# PWRBankCharger.net
KiCad netlist of a schematic drawn in Altium Designer
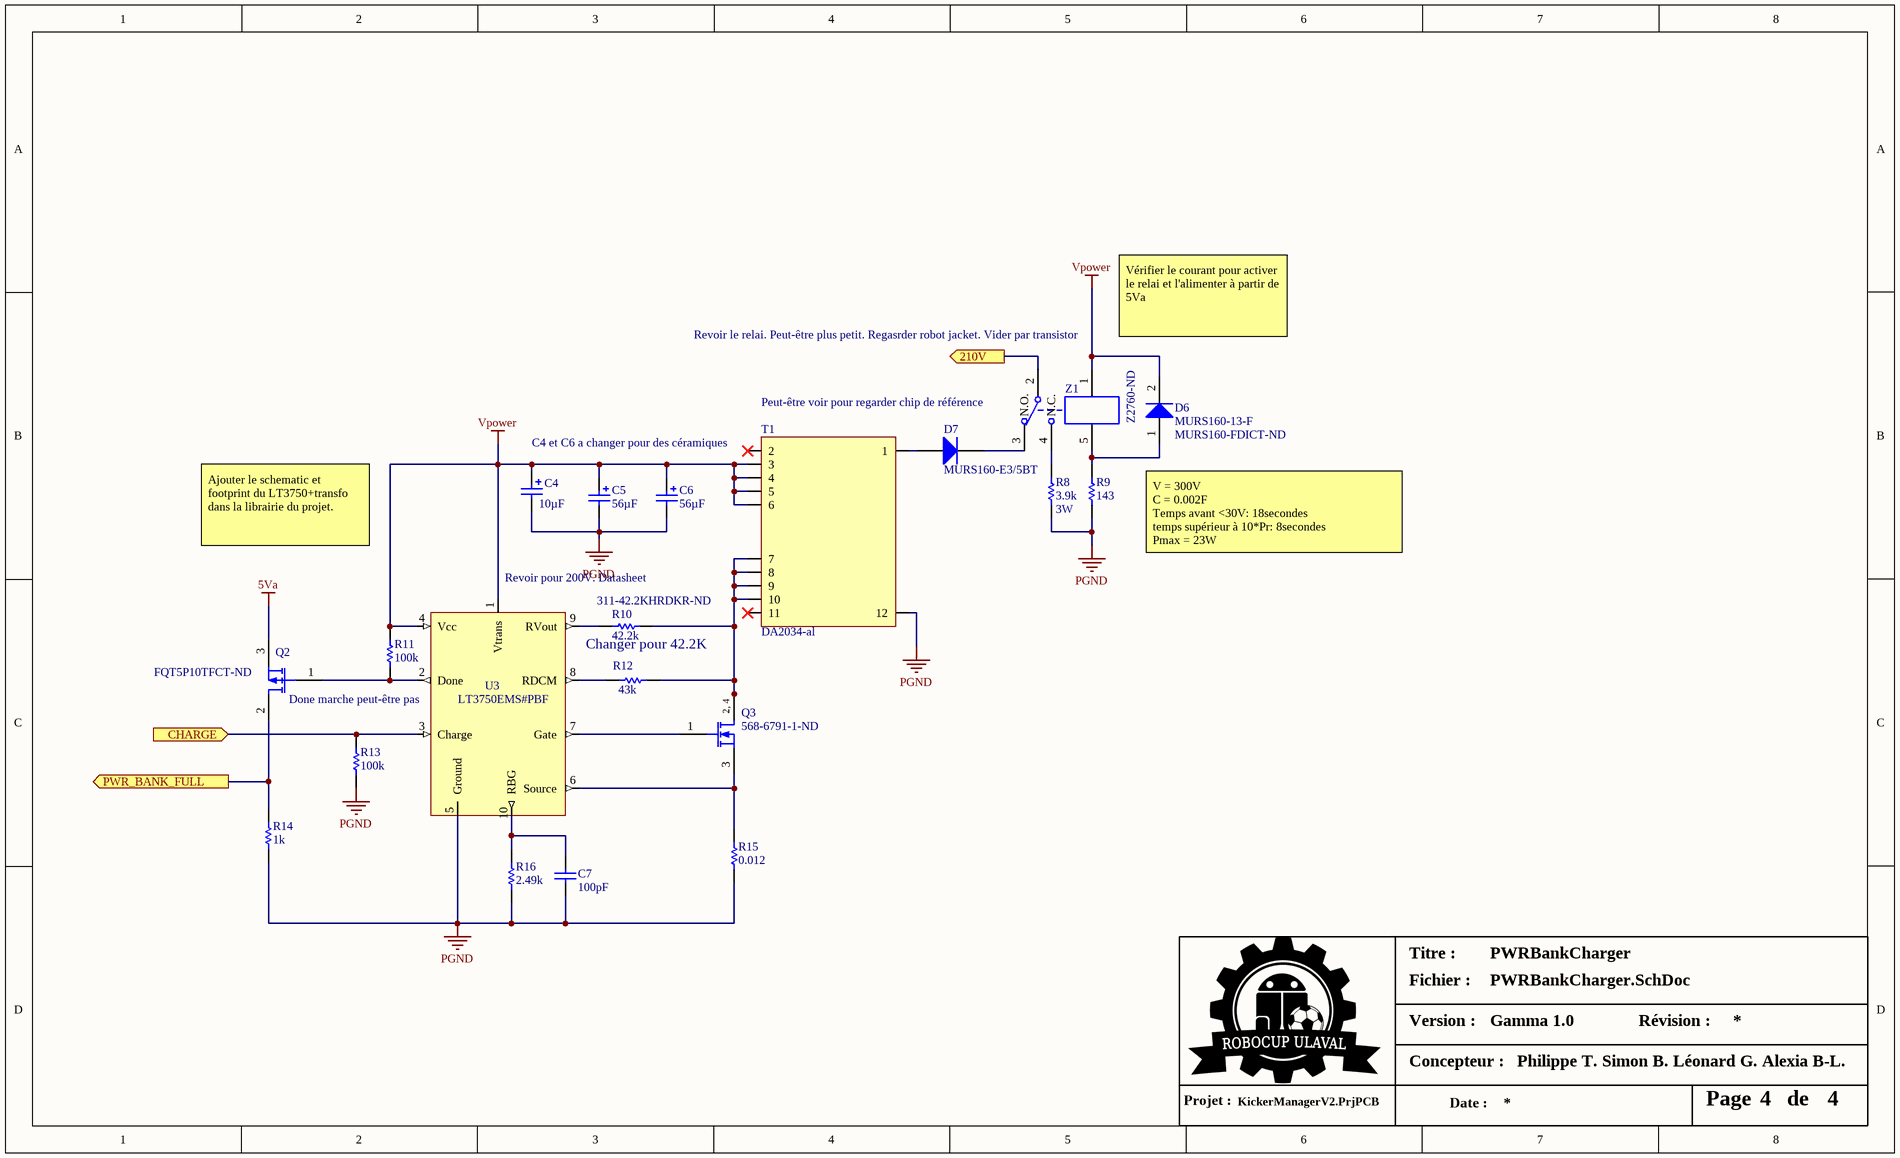
[diagram p0: PWRBankCharger.SchDoc]

(export (version "E")
  (design (tool "Eeschema 10.0.6"))
  (components
    (comp (ref "C4")
      (value "865230340001")
      (footprint "0603")
      (description "CAP 10 UF 20% 16 V")
      (fields
        (field (name "MANUFACTURER") "Wurth Electronics Inc")
        (field (name "CAPACITANCE") "10µF")
        (field (name "TOLERANCE") "±20%")
      )
      (libsource (lib "ResCap") (part "865230340001"))
    )
    (comp (ref "C5")
      (value "865080545010")
      (footprint "CAP 6.6x6.6mm")
      (description "CAP 56 UF 20% 35 V")
      (fields
        (field (name "MANUFACTURER") "Wurth Electronics Inc")
        (field (name "TOLERANCE") "±20%")
        (field (name "CAPACITANCE") "56µF")
      )
      (libsource (lib "ResCap") (part "865080545010"))
    )
    (comp (ref "C6")
      (value "865080545010")
      (footprint "0603")
      (description "CAP 56 UF 20% 35 V")
      (fields
        (field (name "MANUFACTURER") "Wurth Electronics Inc")
        (field (name "TOLERANCE") "±20%")
        (field (name "CAPACITANCE") "56µF")
      )
      (libsource (lib "ResCap") (part "865080545010"))
    )
    (comp (ref "C7")
      (value "CL10B101KB8NNNC")
      (footprint "0603")
      (description "CAP CER 100PF 50V X7R 0603")
      (fields
        (field (name "MANUFACTURER") "Samsung Electro-Mechanics America, Inc.")
        (field (name "TOLERANCE") "±10%")
        (field (name "CAPACITANCE") "100pF")
      )
      (libsource (lib "ResCap") (part "CL10B101KB8NNNC"))
    )
    (comp (ref "D6")
      (value "MURS160-13-F")
      (footprint "SMB")
      (description "DIODE GEN PURP 600V 1A SMB")
      (fields
        (field (name "MANUFACTURER") "Diodes Incorporated")
        (field (name "SUPPLIER PART NUMBER 1") "MURS160-FDICT-ND")
      )
      (libsource (lib "gamma_gestionkicker") (part "MURS160-13-F"))
    )
    (comp (ref "D7")
      (value "MURS160-E3/5BT")
      (footprint "SMB")
      (description "DIODE GEN PURP 600V 2A DO214AA")
      (fields (field (name "MANUFACTURER") "Vishay Semiconductor Diodes Division"))
      (libsource (lib "gamma_gestionkicker") (part "MURS160-E3/5BT"))
    )
    (comp (ref "Q2")
      (value "FQT5P10TF")
      (footprint "SOT-223")
      (description "MOSFET P-CH 100V 1A SOT-223")
      (fields
        (field (name "MANUFACTURER") "Fairchild Semiconductor")
        (field (name "SUPPLIER PART NUMBER 1") "FQT5P10TFCT-ND")
      )
      (libsource (lib "gamma_gestionkicker") (part "FQT5P10TF"))
    )
    (comp (ref "Q3")
      (value "PHT6NQ10T,135")
      (footprint "SOT-223")
      (description "MOSFET N-CH 100V 3A SOT223")
      (fields
        (field (name "MANUFACTURER") "NXP Semiconductors")
        (field (name "SUPPLIER PART NUMBER 1") "568-6791-1-ND")
      )
      (libsource (lib "gamma_gestionkicker") (part "PHT6NQ10T,135"))
    )
    (comp (ref "R8")
      (value "RWM04103901JR15E1")
      (footprint "RWM4x10")
      (description "RES WIREWOUND 3.9K OHM 3W")
      (fields
        (field (name "MANUFACTURER") "Vishay Sfernice")
        (field (name "TOLERANCE") "±5%")
        (field (name "RESISTANCE (OHMS)") "3.9k")
        (field (name "POWER (WATTS)") "3W")
      )
      (libsource (lib "gamma_gestionkicker") (part "RWM04103901JR15E1"))
    )
    (comp (ref "R9")
      (value "CRCW1206143RFKEA")
      (footprint "1206")
      (description "RES SMD 143 OHM 1% 1/4W 1206")
      (fields
        (field (name "MANUFACTURER") "Vishay Dale")
        (field (name "TOLERANCE") "±1%")
        (field (name "RESISTANCE (OHMS)") "143")
      )
      (libsource (lib "ResCap") (part "CRCW1206143RFKEA"))
    )
    (comp (ref "R10")
      (value "RC0603FR-0760K4L")
      (footprint "0603")
      (description "RES SMD 42.2K OHM 1% 1/10W 0603")
      (fields
        (field (name "MANUFACTURER") "Yageo")
        (field (name "TOLERANCE") "±1%")
        (field (name "RESISTANCE (OHMS)") "42.2k")
        (field (name "SUPPLIER PART NUMBER 1") "311-42.2KHRDKR-ND")
      )
      (libsource (lib "ResCap") (part "RC0603FR-0760K4L"))
    )
    (comp (ref "R11")
      (value "RC0603JR-07100KL")
      (footprint "0603")
      (description "RES SMD 100K OHM 5% 1/10W 0603")
      (fields
        (field (name "MANUFACTURER") "Yageo")
        (field (name "TOLERANCE") "±5%")
        (field (name "RESISTANCE (OHMS)") "100k")
      )
      (libsource (lib "ResCap") (part "RC0603JR-07100KL"))
    )
    (comp (ref "R12")
      (value "RC0603JR-0743KL")
      (footprint "0603")
      (description "RES SMD 43K OHM 5% 1/10W 0603")
      (fields
        (field (name "MANUFACTURER") "Yageo")
        (field (name "TOLERANCE") "±5%")
        (field (name "RESISTANCE (OHMS)") "43k")
      )
      (libsource (lib "ResCap") (part "RC0603JR-0743KL"))
    )
    (comp (ref "R13")
      (value "RC0603JR-07100KL")
      (footprint "0603")
      (description "RES SMD 100K OHM 5% 1/10W 0603")
      (fields
        (field (name "MANUFACTURER") "Yageo")
        (field (name "TOLERANCE") "±5%")
        (field (name "RESISTANCE (OHMS)") "100k")
      )
      (libsource (lib "ResCap") (part "RC0603JR-07100KL"))
    )
    (comp (ref "R14")
      (value "RC0603JR-071KL")
      (footprint "0603")
      (description "RES SMD 1K OHM 5% 1/10W 0603")
      (fields
        (field (name "MANUFACTURER") "Yageo")
        (field (name "TOLERANCE") "±5%")
        (field (name "RESISTANCE (OHMS)") "1k")
      )
      (libsource (lib "ResCap") (part "RC0603JR-071KL"))
    )
    (comp (ref "R15")
      (value "RL1220T-R012-J")
      (footprint "0805")
      (description "RES SMD 0.012 OHM 5% 1/4W 0805")
      (fields
        (field (name "MANUFACTURER") "Susumu")
        (field (name "TOLERANCE") "±5%")
        (field (name "RESISTANCE (OHMS)") "0.012")
      )
      (libsource (lib "ResCap") (part "RL1220T-R012-J"))
    )
    (comp (ref "R16")
      (value "RC0603FR-072K49L")
      (footprint "0603")
      (description "RES SMD 2.49K OHM 1% 1/10W 0603")
      (fields
        (field (name "MANUFACTURER") "Yageo")
        (field (name "TOLERANCE") "±1%")
        (field (name "RESISTANCE (OHMS)") "2.49k")
      )
      (libsource (lib "ResCap") (part "RC0603FR-072K49L"))
    )
    (comp (ref "T1")
      (value "DA2034-al")
      (footprint "da2034")
      (libsource (lib "da2034-al") (part "DA2034-al"))
    )
    (comp (ref "U3")
      (value "LT3750EMS#PBF")
      (footprint "MSOP-10")
      (description "IC CONVERTER 10-MSOP")
      (fields (field (name "MANUFACTURER") "Linear Technology"))
      (libsource (lib "gamma_gestionkicker") (part "LT3750EMS#PBF"))
    )
    (comp (ref "Z1")
      (value "G6RL-1 DC12")
      (footprint "G6RL")
      (description "RELAY GEN PURPOSE SPDT 8A 12V")
      (fields
        (field (name "MANUFACTURER") "Omron Electronics Inc-EMC Div")
        (field (name "SUPPLIER PART NUMBER 1") "Z2760-ND")
      )
      (libsource (lib "gamma_gestionkicker") (part "G6RL-1 DC12"))
    )
  )
  (nets
    (net (code "1") (name "/210V") (class "Default")
      (node (ref "Z1") (pin "2") (pinfunction "Signal_Input_2") (pintype "passive"))
    )
    (net (code "2") (name "/CHARGE") (class "Default")
      (node (ref "R13") (pin "2") (pinfunction "2_2") (pintype "passive"))
      (node (ref "U3") (pin "3") (pinfunction "Charge_3") (pintype "input"))
    )
    (net (code "3") (name "/PWR_BANK_FULL") (class "Default")
      (node (ref "Q2") (pin "2") (pinfunction "D_2") (pintype "passive"))
      (node (ref "R14") (pin "2") (pinfunction "2_2") (pintype "passive"))
    )
    (net (code "4") (name "5Va") (class "Default")
      (node (ref "Q2") (pin "3") (pinfunction "S_3") (pintype "passive"))
    )
    (net (code "5") (name "Net-(D6-A)") (class "Default")
      (node (ref "D6") (pin "1") (pinfunction "A_1") (pintype "passive"))
      (node (ref "R9") (pin "1") (pinfunction "1_1") (pintype "passive"))
      (node (ref "Z1") (pin "5") (pinfunction "Coil_Input_-_5") (pintype "passive"))
    )
    (net (code "6") (name "Net-(D7-A)") (class "Default")
      (node (ref "D7") (pin "1") (pinfunction "A_1") (pintype "passive"))
      (node (ref "T1") (pin "1") (pinfunction "1_1") (pintype "passive"))
    )
    (net (code "7") (name "Net-(D7-K)") (class "Default")
      (node (ref "D7") (pin "2") (pinfunction "K_2") (pintype "passive"))
      (node (ref "Z1") (pin "3") (pinfunction "N.O._3") (pintype "passive"))
    )
    (net (code "8") (name "Net-(Q2-G)") (class "Default")
      (node (ref "Q2") (pin "1") (pinfunction "G_1") (pintype "passive"))
      (node (ref "R11") (pin "1") (pinfunction "1_1") (pintype "passive"))
      (node (ref "U3") (pin "2") (pinfunction "Done_2") (pintype "output"))
    )
    (net (code "9") (name "Net-(Q3-D-Pad2)") (class "Default")
      (node (ref "Q3") (pin "2") (pinfunction "D_2") (pintype "passive"))
      (node (ref "Q3") (pin "4") (pinfunction "D_4") (pintype "passive"))
      (node (ref "R10") (pin "2") (pinfunction "2_2") (pintype "passive"))
      (node (ref "R12") (pin "1") (pinfunction "1_1") (pintype "passive"))
      (node (ref "T1") (pin "10") (pinfunction "10_10") (pintype "passive"))
      (node (ref "T1") (pin "7") (pinfunction "7_7") (pintype "passive"))
      (node (ref "T1") (pin "8") (pinfunction "8_8") (pintype "passive"))
      (node (ref "T1") (pin "9") (pinfunction "9_9") (pintype "passive"))
    )
    (net (code "10") (name "Net-(Q3-G)") (class "Default")
      (node (ref "Q3") (pin "1") (pinfunction "G_1") (pintype "passive"))
      (node (ref "U3") (pin "7") (pinfunction "Gate_7") (pintype "output"))
    )
    (net (code "11") (name "Net-(Q3-S)") (class "Default")
      (node (ref "Q3") (pin "3") (pinfunction "S_3") (pintype "passive"))
      (node (ref "R15") (pin "2") (pinfunction "2_2") (pintype "passive"))
      (node (ref "U3") (pin "6") (pinfunction "Source_6") (pintype "output"))
    )
    (net (code "12") (name "Net-(U3-RBG)") (class "Default")
      (node (ref "C7") (pin "1") (pinfunction "1_1") (pintype "passive"))
      (node (ref "R16") (pin "2") (pinfunction "2_2") (pintype "passive"))
      (node (ref "U3") (pin "10") (pinfunction "RBG_10") (pintype "output"))
    )
    (net (code "13") (name "Net-(U3-RDCM)") (class "Default")
      (node (ref "R12") (pin "2") (pinfunction "2_2") (pintype "passive"))
      (node (ref "U3") (pin "8") (pinfunction "RDCM_8") (pintype "output"))
    )
    (net (code "14") (name "Net-(U3-RVout)") (class "Default")
      (node (ref "R10") (pin "1") (pinfunction "1_1") (pintype "passive"))
      (node (ref "U3") (pin "9") (pinfunction "RVout_9") (pintype "output"))
    )
    (net (code "15") (name "Net-(Z1-N.C.)") (class "Default")
      (node (ref "R8") (pin "2") (pinfunction "2_2") (pintype "passive"))
      (node (ref "Z1") (pin "4") (pinfunction "N.C._4") (pintype "passive"))
    )
    (net (code "16") (name "PGND") (class "Default")
      (node (ref "C4") (pin "2") (pinfunction "2_2") (pintype "passive"))
      (node (ref "C5") (pin "2") (pinfunction "2_2") (pintype "passive"))
      (node (ref "C6") (pin "2") (pinfunction "2_2") (pintype "passive"))
      (node (ref "C7") (pin "2") (pinfunction "2_2") (pintype "passive"))
      (node (ref "R13") (pin "1") (pinfunction "1_1") (pintype "passive"))
      (node (ref "R14") (pin "1") (pinfunction "1_1") (pintype "passive"))
      (node (ref "R15") (pin "1") (pinfunction "1_1") (pintype "passive"))
      (node (ref "R16") (pin "1") (pinfunction "1_1") (pintype "passive"))
      (node (ref "R8") (pin "1") (pinfunction "1_1") (pintype "passive"))
      (node (ref "R9") (pin "2") (pinfunction "2_2") (pintype "passive"))
      (node (ref "T1") (pin "12") (pinfunction "12_12") (pintype "passive"))
      (node (ref "U3") (pin "5") (pinfunction "Ground_5") (pintype "power_in"))
    )
    (net (code "17") (name "Vpower") (class "Default")
      (node (ref "C4") (pin "1") (pinfunction "1_1") (pintype "passive"))
      (node (ref "C5") (pin "1") (pinfunction "1_1") (pintype "passive"))
      (node (ref "C6") (pin "1") (pinfunction "1_1") (pintype "passive"))
      (node (ref "D6") (pin "2") (pinfunction "K_2") (pintype "passive"))
      (node (ref "R11") (pin "2") (pinfunction "2_2") (pintype "passive"))
      (node (ref "T1") (pin "3") (pinfunction "3_3") (pintype "passive"))
      (node (ref "T1") (pin "4") (pinfunction "4_4") (pintype "passive"))
      (node (ref "T1") (pin "5") (pinfunction "5_5") (pintype "passive"))
      (node (ref "T1") (pin "6") (pinfunction "6_6") (pintype "passive"))
      (node (ref "U3") (pin "1") (pinfunction "Vtrans_1") (pintype "bidirectional"))
      (node (ref "U3") (pin "4") (pinfunction "Vcc_4") (pintype "input"))
      (node (ref "Z1") (pin "1") (pinfunction "Coil_Input_+_1") (pintype "passive"))
    )
    (net (code "18") (name "unconnected-(T1-Pad2)") (class "Default")
      (node (ref "T1") (pin "2") (pinfunction "2_2") (pintype "passive+no_connect"))
    )
    (net (code "19") (name "unconnected-(T1-Pad11)") (class "Default")
      (node (ref "T1") (pin "11") (pinfunction "11_11") (pintype "passive+no_connect"))
    )
  )
)
